# headstage-programmer.net
KiCad netlist of a schematic drawn in EAGLE
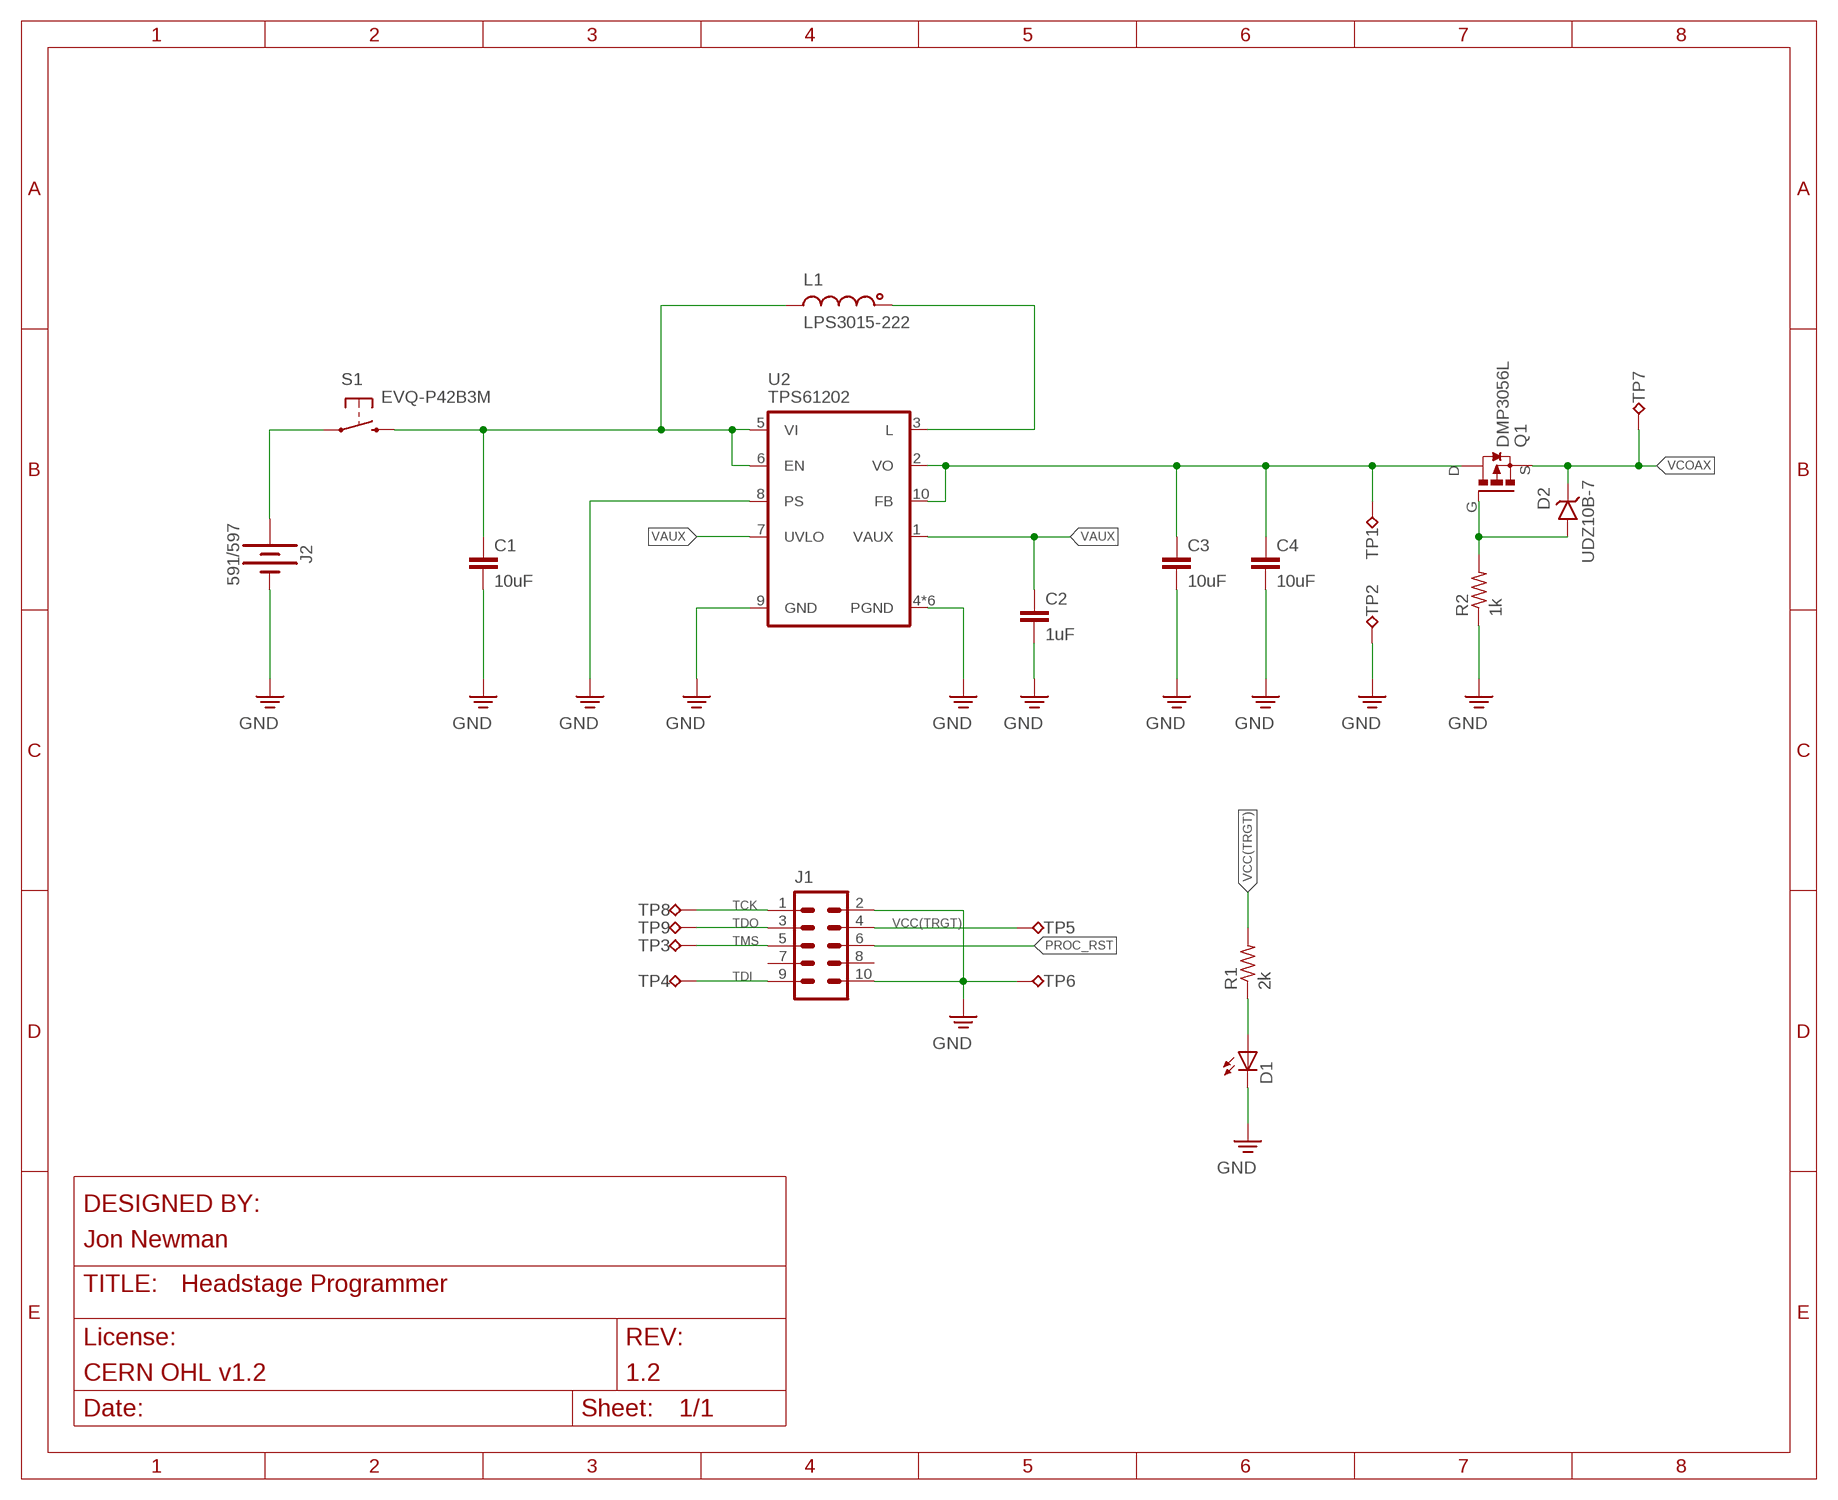
[diagram p0: schematic, sheet 1]

(export (version "E")
  (design (tool "Eeschema 10.0.6"))
  (components
    (comp (ref "C1")
      (value "10uF")
      (footprint "eagle-import:0805")
      (fields (field (name "PARTNO") "C2012X5R1Cxxxxxxx"))
      (libsource (lib "eagle-import") (part "C_0805"))
    )
    (comp (ref "C2")
      (value "1uF")
      (footprint "eagle-import:0603")
      (libsource (lib "eagle-import") (part "C_0603"))
    )
    (comp (ref "C3")
      (value "10uF")
      (footprint "eagle-import:0805")
      (fields (field (name "PARTNO") "C2012X5R1Cxxxxxxx"))
      (libsource (lib "eagle-import") (part "C_0805"))
    )
    (comp (ref "C4")
      (value "10uF")
      (footprint "eagle-import:0805")
      (fields (field (name "PARTNO") "C2012X5R1Cxxxxxxx"))
      (libsource (lib "eagle-import") (part "C_0805"))
    )
    (comp (ref "D1")
      (value "LED_0603")
      (footprint "eagle-import:LED-0603")
      (libsource (lib "eagle-import") (part "LED_0603"))
    )
    (comp (ref "D2")
      (value "UDZ10B-7")
      (footprint "eagle-import:SOD-323")
      (libsource (lib "eagle-import") (part "Z-DIODE_SOD-323"))
    )
    (comp (ref "J1")
      (value "302-S101")
      (footprint "eagle-import:2X05_IDC")
      (libsource (lib "eagle-import") (part "PINHD-2X5_IDC"))
    )
    (comp (ref "J2")
      (value "591/597")
      (footprint "eagle-import:597_591_AAA-HOLDER")
      (libsource (lib "eagle-import") (part "BATTERY_597/591"))
    )
    (comp (ref "L1")
      (value "LPS3015-222")
      (footprint "eagle-import:LPS3015")
      (libsource (lib "eagle-import") (part "L_LPS3015"))
    )
    (comp (ref "Q1")
      (value "DMP3056L")
      (footprint "eagle-import:SOT23-GSD")
      (fields (field (name "PARTNO") "DMP3056L-7"))
      (libsource (lib "eagle-import") (part "P-MOSFET_SOT23-GSD"))
    )
    (comp (ref "R1")
      (value "2k")
      (footprint "eagle-import:0603")
      (fields (field (name "MPN") "ERJ-3EKFxxxxV"))
      (libsource (lib "eagle-import") (part "R_0603"))
    )
    (comp (ref "R2")
      (value "1k")
      (footprint "eagle-import:0603")
      (fields (field (name "MPN") "ERJ-3EKFxxxxV"))
      (libsource (lib "eagle-import") (part "R_0603"))
    )
    (comp (ref "S1")
      (value "EVQ-P42B3M")
      (footprint "eagle-import:EVQP4")
      (libsource (lib "eagle-import") (part "SPST_TACT2_EVQP4"))
    )
    (comp (ref "TP1")
      (value "TP_1MM")
      (footprint "eagle-import:TESTPOINT_1MM")
      (libsource (lib "eagle-import") (part "TP_1MM"))
    )
    (comp (ref "TP2")
      (value "TP_1MM")
      (footprint "eagle-import:TESTPOINT_1MM")
      (libsource (lib "eagle-import") (part "TP_1MM"))
    )
    (comp (ref "TP3")
      (value "TP_S500-6350-P2")
      (footprint "eagle-import:POGO_S500-6350-P2")
      (libsource (lib "eagle-import") (part "TP_S500-6350-P2"))
    )
    (comp (ref "TP4")
      (value "TP_S500-6350-P2")
      (footprint "eagle-import:POGO_S500-6350-P2")
      (libsource (lib "eagle-import") (part "TP_S500-6350-P2"))
    )
    (comp (ref "TP5")
      (value "TP_S500-6350-P2")
      (footprint "eagle-import:POGO_S500-6350-P2")
      (libsource (lib "eagle-import") (part "TP_S500-6350-P2"))
    )
    (comp (ref "TP6")
      (value "TP_S500-6350-P2")
      (footprint "eagle-import:POGO_S500-6350-P2")
      (libsource (lib "eagle-import") (part "TP_S500-6350-P2"))
    )
    (comp (ref "TP7")
      (value "TP_S500-6350-P2")
      (footprint "eagle-import:POGO_S500-6350-P2")
      (libsource (lib "eagle-import") (part "TP_S500-6350-P2"))
    )
    (comp (ref "TP8")
      (value "TP_S500-6350-P2")
      (footprint "eagle-import:POGO_S500-6350-P2")
      (libsource (lib "eagle-import") (part "TP_S500-6350-P2"))
    )
    (comp (ref "TP9")
      (value "TP_S500-6350-P2")
      (footprint "eagle-import:POGO_S500-6350-P2")
      (libsource (lib "eagle-import") (part "TP_S500-6350-P2"))
    )
    (comp (ref "U2")
      (value "TPS61202")
      (footprint "eagle-import:PWSON-N10+4-3X3")
      (libsource (lib "eagle-import") (part "TPS61200"))
    )
  )
  (nets
    (net (code "1") (name "/TCK") (class "Default")
      (node (ref "J1") (pin "1") (pinfunction "1_1") (pintype "passive"))
      (node (ref "TP8") (pin "P$1") (pinfunction "TP_P$1") (pintype "bidirectional"))
    )
    (net (code "2") (name "/TDI") (class "Default")
      (node (ref "J1") (pin "9") (pinfunction "9_9") (pintype "passive"))
      (node (ref "TP4") (pin "P$1") (pinfunction "TP_P$1") (pintype "bidirectional"))
    )
    (net (code "3") (name "/TDO") (class "Default")
      (node (ref "J1") (pin "3") (pinfunction "3_3") (pintype "passive"))
      (node (ref "TP9") (pin "P$1") (pinfunction "TP_P$1") (pintype "bidirectional"))
    )
    (net (code "4") (name "/TMS") (class "Default")
      (node (ref "J1") (pin "5") (pinfunction "5_5") (pintype "passive"))
      (node (ref "TP3") (pin "P$1") (pinfunction "TP_P$1") (pintype "bidirectional"))
    )
    (net (code "5") (name "GND") (class "Default")
      (node (ref "C1") (pin "2") (pinfunction "2_2") (pintype "passive"))
      (node (ref "C2") (pin "2") (pinfunction "2_2") (pintype "passive"))
      (node (ref "C3") (pin "2") (pinfunction "2_2") (pintype "passive"))
      (node (ref "C4") (pin "2") (pinfunction "2_2") (pintype "passive"))
      (node (ref "D1") (pin "C") (pinfunction "C_C") (pintype "passive"))
      (node (ref "J1") (pin "10") (pinfunction "10_10") (pintype "passive"))
      (node (ref "J1") (pin "2") (pinfunction "2_2") (pintype "passive"))
      (node (ref "J2") (pin "-1") (pinfunction "-_-1") (pintype "power_in"))
      (node (ref "J2") (pin "-2") (pinfunction "-_-2") (pintype "power_in"))
      (node (ref "J2") (pin "-3") (pinfunction "-_-3") (pintype "power_in"))
      (node (ref "R2") (pin "1") (pinfunction "1_1") (pintype "passive"))
      (node (ref "TP2") (pin "1") (pinfunction "TP_1") (pintype "bidirectional"))
      (node (ref "TP6") (pin "P$1") (pinfunction "TP_P$1") (pintype "bidirectional"))
      (node (ref "U2") (pin "4") (pinfunction "PGND_4") (pintype "power_in"))
      (node (ref "U2") (pin "8") (pinfunction "PS_8") (pintype "input"))
      (node (ref "U2") (pin "9") (pinfunction "GND_9") (pintype "power_in"))
      (node (ref "U2") (pin "PAD") (pinfunction "PGND_PAD") (pintype "power_in"))
      (node (ref "U2") (pin "PAD1") (pinfunction "PGND_PAD1") (pintype "power_in"))
      (node (ref "U2") (pin "PAD2") (pinfunction "PGND_PAD2") (pintype "power_in"))
      (node (ref "U2") (pin "PAD3") (pinfunction "PGND_PAD3") (pintype "power_in"))
      (node (ref "U2") (pin "PAD4") (pinfunction "PGND_PAD4") (pintype "power_in"))
    )
    (net (code "6") (name "Net-(D1-PadA)") (class "Default")
      (node (ref "D1") (pin "A") (pinfunction "A_A") (pintype "passive"))
      (node (ref "R1") (pin "1") (pinfunction "1_1") (pintype "passive"))
    )
    (net (code "7") (name "Net-(D2-PadA)") (class "Default")
      (node (ref "D2") (pin "A") (pinfunction "A_A") (pintype "passive"))
      (node (ref "Q1") (pin "G") (pinfunction "G_G") (pintype "bidirectional"))
      (node (ref "R2") (pin "2") (pinfunction "2_2") (pintype "passive"))
    )
    (net (code "8") (name "Net-(S1-P)") (class "Default")
      (node (ref "J2") (pin "+1") (pinfunction "+_+1") (pintype "power_in"))
      (node (ref "J2") (pin "+2") (pinfunction "+_+2") (pintype "power_in"))
      (node (ref "J2") (pin "+3") (pinfunction "+_+3") (pintype "power_in"))
      (node (ref "S1") (pin "1") (pinfunction "P_1") (pintype "passive"))
    )
    (net (code "9") (name "Net-(S1-S)") (class "Default")
      (node (ref "C1") (pin "1") (pinfunction "1_1") (pintype "passive"))
      (node (ref "L1") (pin "2") (pinfunction "2_2") (pintype "passive"))
      (node (ref "S1") (pin "2") (pinfunction "S_2") (pintype "passive"))
      (node (ref "U2") (pin "5") (pinfunction "VI_5") (pintype "power_in"))
      (node (ref "U2") (pin "6") (pinfunction "EN_6") (pintype "input"))
    )
    (net (code "10") (name "Net-(TP1-TP)") (class "Default")
      (node (ref "C3") (pin "1") (pinfunction "1_1") (pintype "passive"))
      (node (ref "C4") (pin "1") (pinfunction "1_1") (pintype "passive"))
      (node (ref "Q1") (pin "D") (pinfunction "D_D") (pintype "bidirectional"))
      (node (ref "TP1") (pin "1") (pinfunction "TP_1") (pintype "bidirectional"))
      (node (ref "U2") (pin "10") (pinfunction "FB_10") (pintype "input"))
      (node (ref "U2") (pin "2") (pinfunction "VO_2") (pintype "power_in"))
    )
    (net (code "11") (name "Net-(U2-L)") (class "Default")
      (node (ref "L1") (pin "1") (pinfunction "1_1") (pintype "passive"))
      (node (ref "U2") (pin "3") (pinfunction "L_3") (pintype "bidirectional"))
    )
    (net (code "12") (name "PROC_RST") (class "Default")
      (node (ref "J1") (pin "6") (pinfunction "6_6") (pintype "passive"))
    )
    (net (code "13") (name "VAUX") (class "Default")
      (node (ref "C2") (pin "1") (pinfunction "1_1") (pintype "passive"))
      (node (ref "U2") (pin "1") (pinfunction "VAUX_1") (pintype "output"))
      (node (ref "U2") (pin "7") (pinfunction "UVLO_7") (pintype "passive"))
    )
    (net (code "14") (name "VCC(TRGT)") (class "Default")
      (node (ref "J1") (pin "4") (pinfunction "4_4") (pintype "passive"))
      (node (ref "R1") (pin "2") (pinfunction "2_2") (pintype "passive"))
      (node (ref "TP5") (pin "P$1") (pinfunction "TP_P$1") (pintype "bidirectional"))
    )
    (net (code "15") (name "VCOAX") (class "Default")
      (node (ref "D2") (pin "C") (pinfunction "C_C") (pintype "passive"))
      (node (ref "Q1") (pin "S") (pinfunction "S_S") (pintype "bidirectional"))
      (node (ref "TP7") (pin "P$1") (pinfunction "TP_P$1") (pintype "bidirectional"))
    )
    (net (code "16") (name "unconnected-(J1-Pad7)") (class "Default")
      (node (ref "J1") (pin "7") (pinfunction "7_7") (pintype "passive"))
    )
    (net (code "17") (name "unconnected-(J1-Pad8)") (class "Default")
      (node (ref "J1") (pin "8") (pinfunction "8_8") (pintype "passive"))
    )
  )
)
